# SPLIT2.net
KiCad netlist of a schematic drawn in Altium Designer
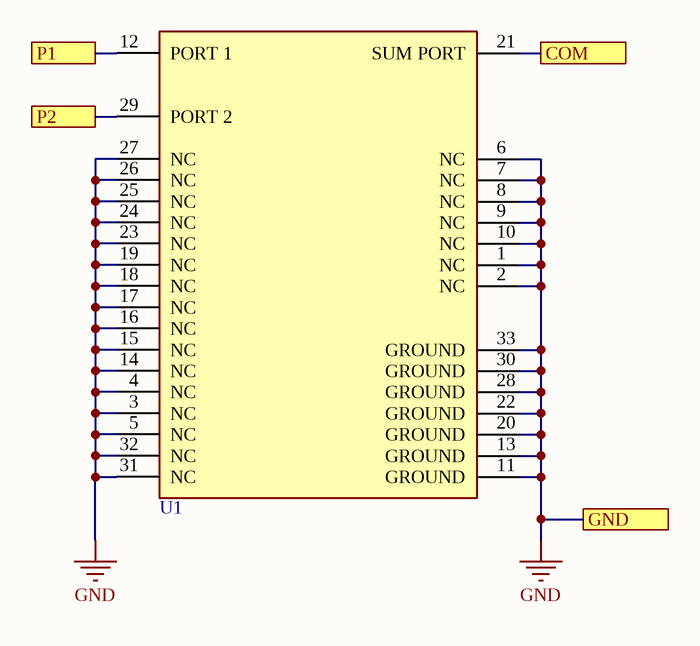
[diagram p0: SPLIT2.SchDoc]

(export (version "E")
  (design (tool "Eeschema 10.0.6"))
  (components
    (comp (ref "U1")
      (value "EP2RKU+")
      (footprint "EP2RKU+")
      (description "2 Ways MMIC Power Splitter, DC - 18000 MHz, 50Ω")
      (libsource (lib "FullyDigital") (part "EP2RKU+"))
    )
  )
  (nets
    (net (code "1") (name "/COM") (class "Default")
      (node (ref "U1") (pin "21") (pinfunction "SUM_PORT_21") (pintype "passive"))
    )
    (net (code "2") (name "/P1") (class "Default")
      (node (ref "U1") (pin "12") (pinfunction "PORT_1_12") (pintype "passive"))
    )
    (net (code "3") (name "/P2") (class "Default")
      (node (ref "U1") (pin "29") (pinfunction "PORT_2_29") (pintype "passive"))
    )
    (net (code "4") (name "GND") (class "Default")
      (node (ref "U1") (pin "1") (pinfunction "NC_1") (pintype "passive"))
      (node (ref "U1") (pin "10") (pinfunction "NC_10") (pintype "passive"))
      (node (ref "U1") (pin "11") (pinfunction "GROUND_11") (pintype "power_in"))
      (node (ref "U1") (pin "13") (pinfunction "GROUND_13") (pintype "power_in"))
      (node (ref "U1") (pin "14") (pinfunction "NC_14") (pintype "passive"))
      (node (ref "U1") (pin "15") (pinfunction "NC_15") (pintype "passive"))
      (node (ref "U1") (pin "16") (pinfunction "NC_16") (pintype "passive"))
      (node (ref "U1") (pin "17") (pinfunction "NC_17") (pintype "passive"))
      (node (ref "U1") (pin "18") (pinfunction "NC_18") (pintype "passive"))
      (node (ref "U1") (pin "19") (pinfunction "NC_19") (pintype "passive"))
      (node (ref "U1") (pin "2") (pinfunction "NC_2") (pintype "passive"))
      (node (ref "U1") (pin "20") (pinfunction "GROUND_20") (pintype "power_in"))
      (node (ref "U1") (pin "22") (pinfunction "GROUND_22") (pintype "power_in"))
      (node (ref "U1") (pin "23") (pinfunction "NC_23") (pintype "passive"))
      (node (ref "U1") (pin "24") (pinfunction "NC_24") (pintype "passive"))
      (node (ref "U1") (pin "25") (pinfunction "NC_25") (pintype "passive"))
      (node (ref "U1") (pin "26") (pinfunction "NC_26") (pintype "passive"))
      (node (ref "U1") (pin "27") (pinfunction "NC_27") (pintype "passive"))
      (node (ref "U1") (pin "28") (pinfunction "GROUND_28") (pintype "passive"))
      (node (ref "U1") (pin "3") (pinfunction "NC_3") (pintype "passive"))
      (node (ref "U1") (pin "30") (pinfunction "GROUND_30") (pintype "power_in"))
      (node (ref "U1") (pin "31") (pinfunction "NC_31") (pintype "passive"))
      (node (ref "U1") (pin "32") (pinfunction "NC_32") (pintype "passive"))
      (node (ref "U1") (pin "33") (pinfunction "GROUND_33") (pintype "power_in"))
      (node (ref "U1") (pin "4") (pinfunction "NC_4") (pintype "passive"))
      (node (ref "U1") (pin "5") (pinfunction "NC_5") (pintype "passive"))
      (node (ref "U1") (pin "6") (pinfunction "NC_6") (pintype "passive"))
      (node (ref "U1") (pin "7") (pinfunction "NC_7") (pintype "passive"))
      (node (ref "U1") (pin "8") (pinfunction "NC_8") (pintype "passive"))
      (node (ref "U1") (pin "9") (pinfunction "NC_9") (pintype "passive"))
    )
  )
)
